# MCU.net
KiCad netlist of a schematic drawn in Altium Designer
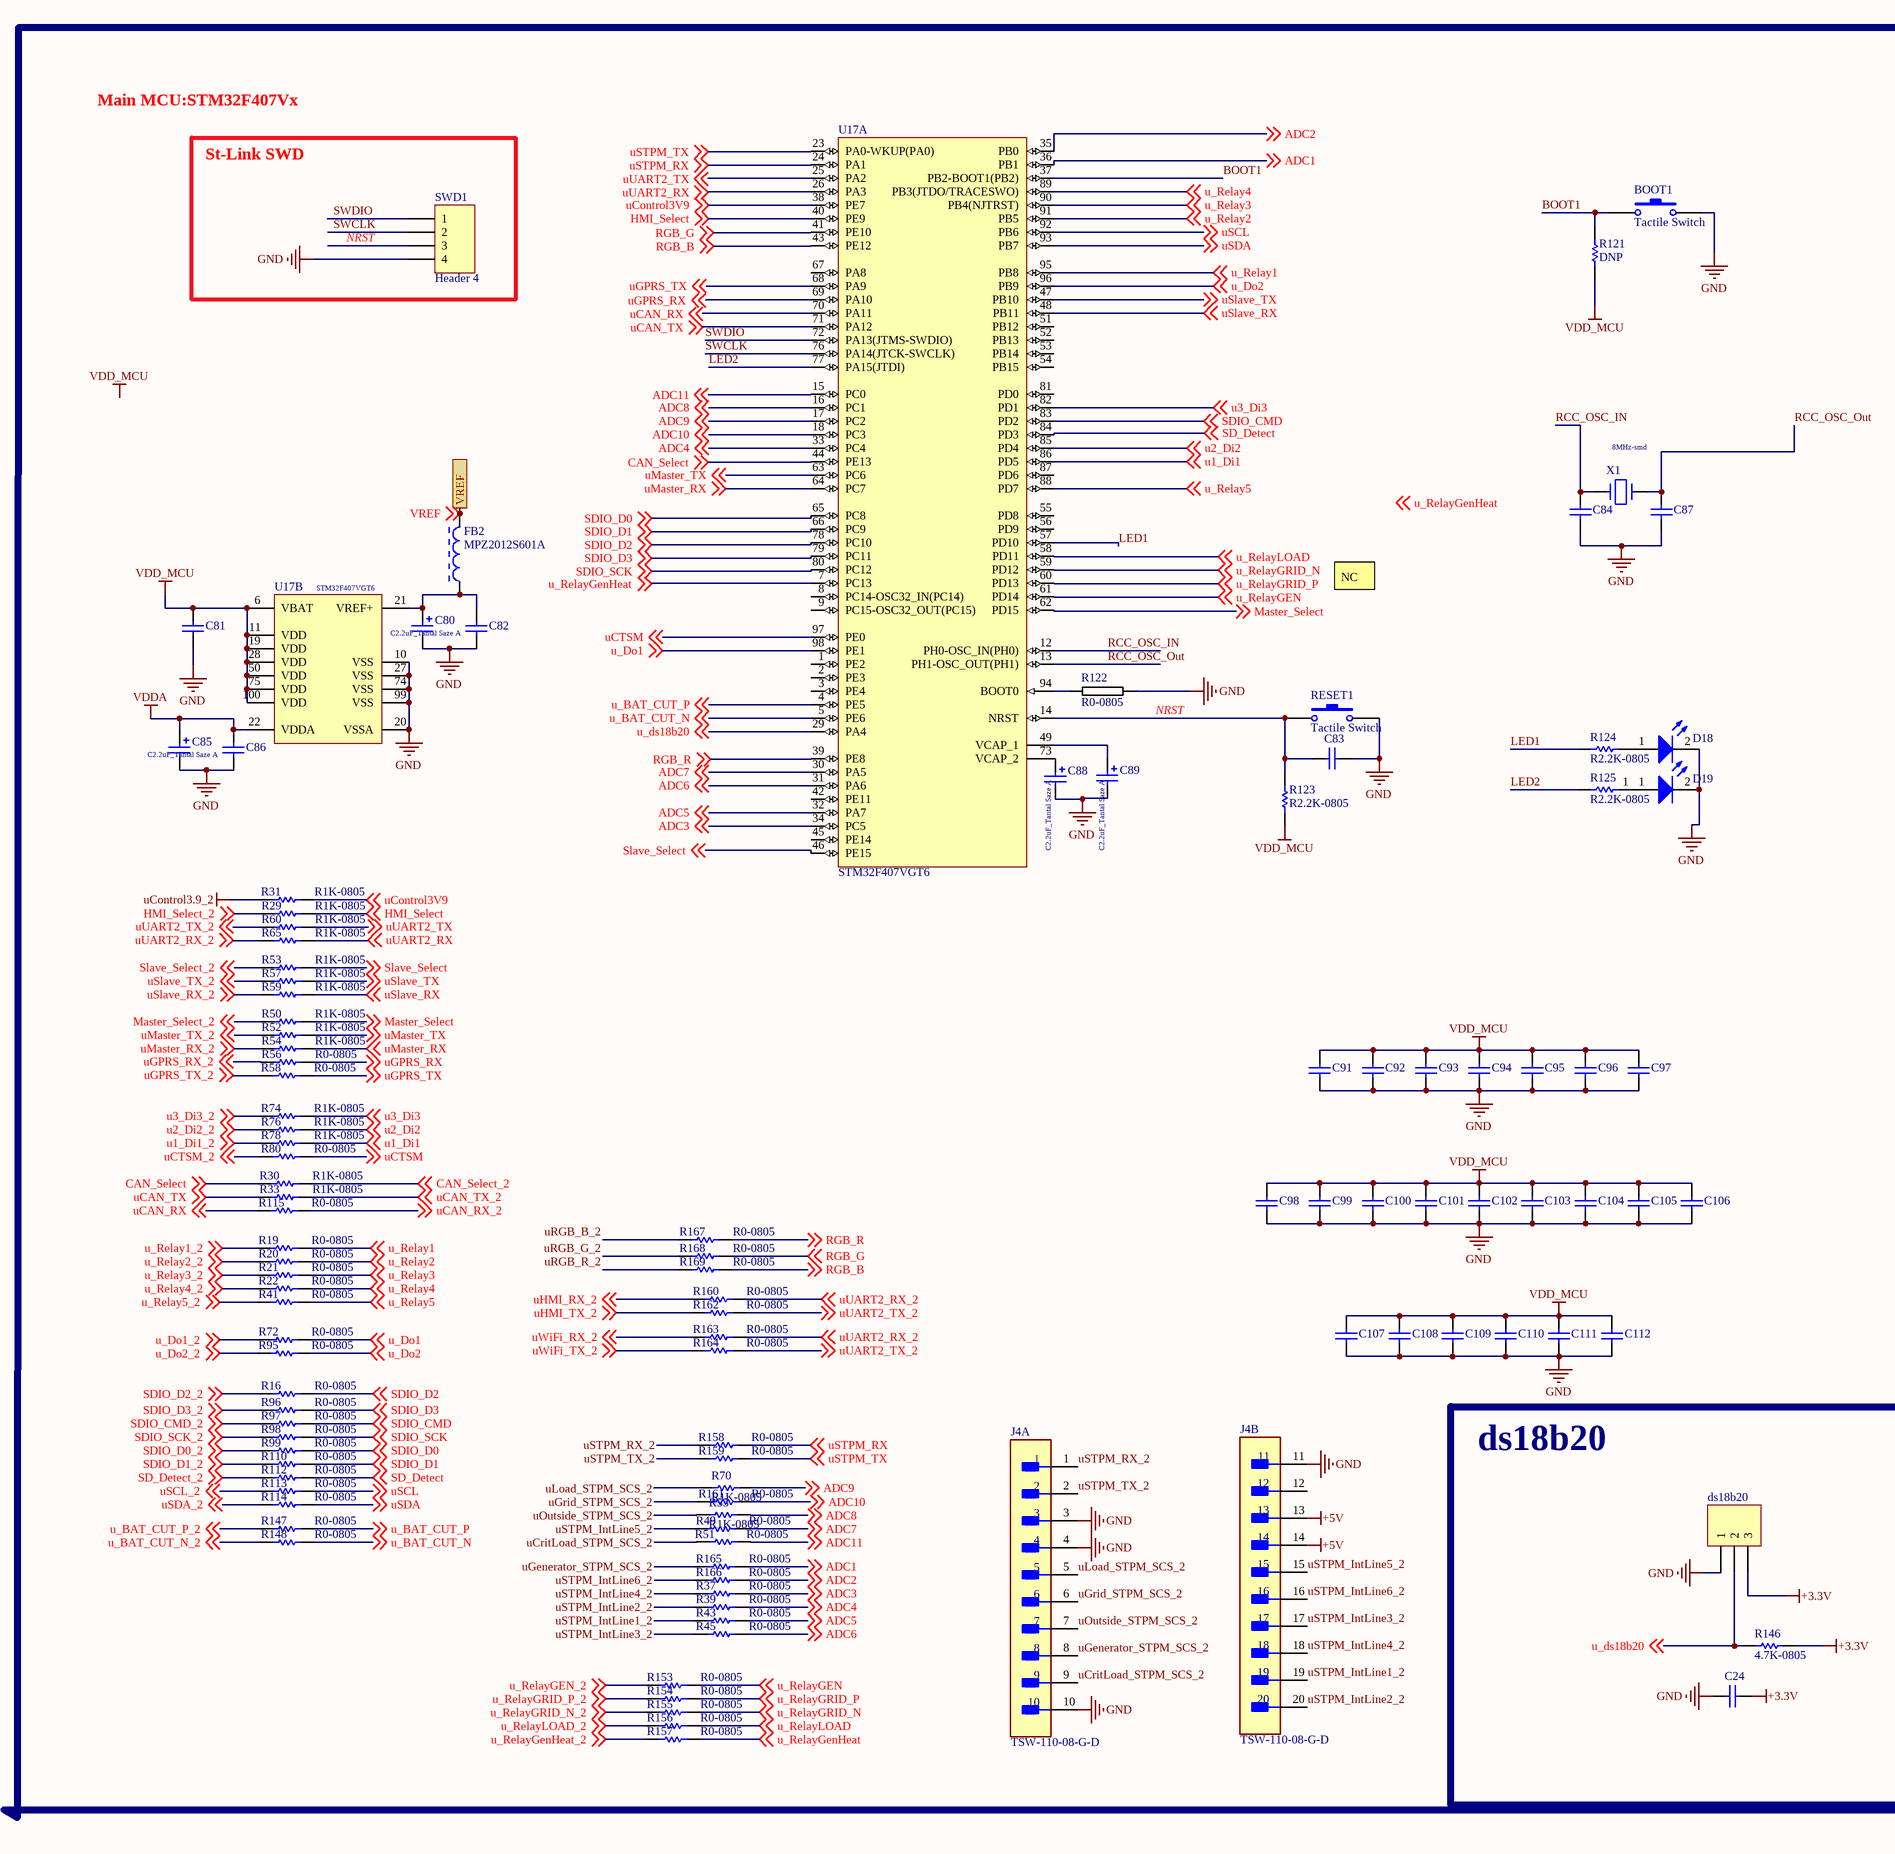
[diagram p0: MCU.SchDoc, left]
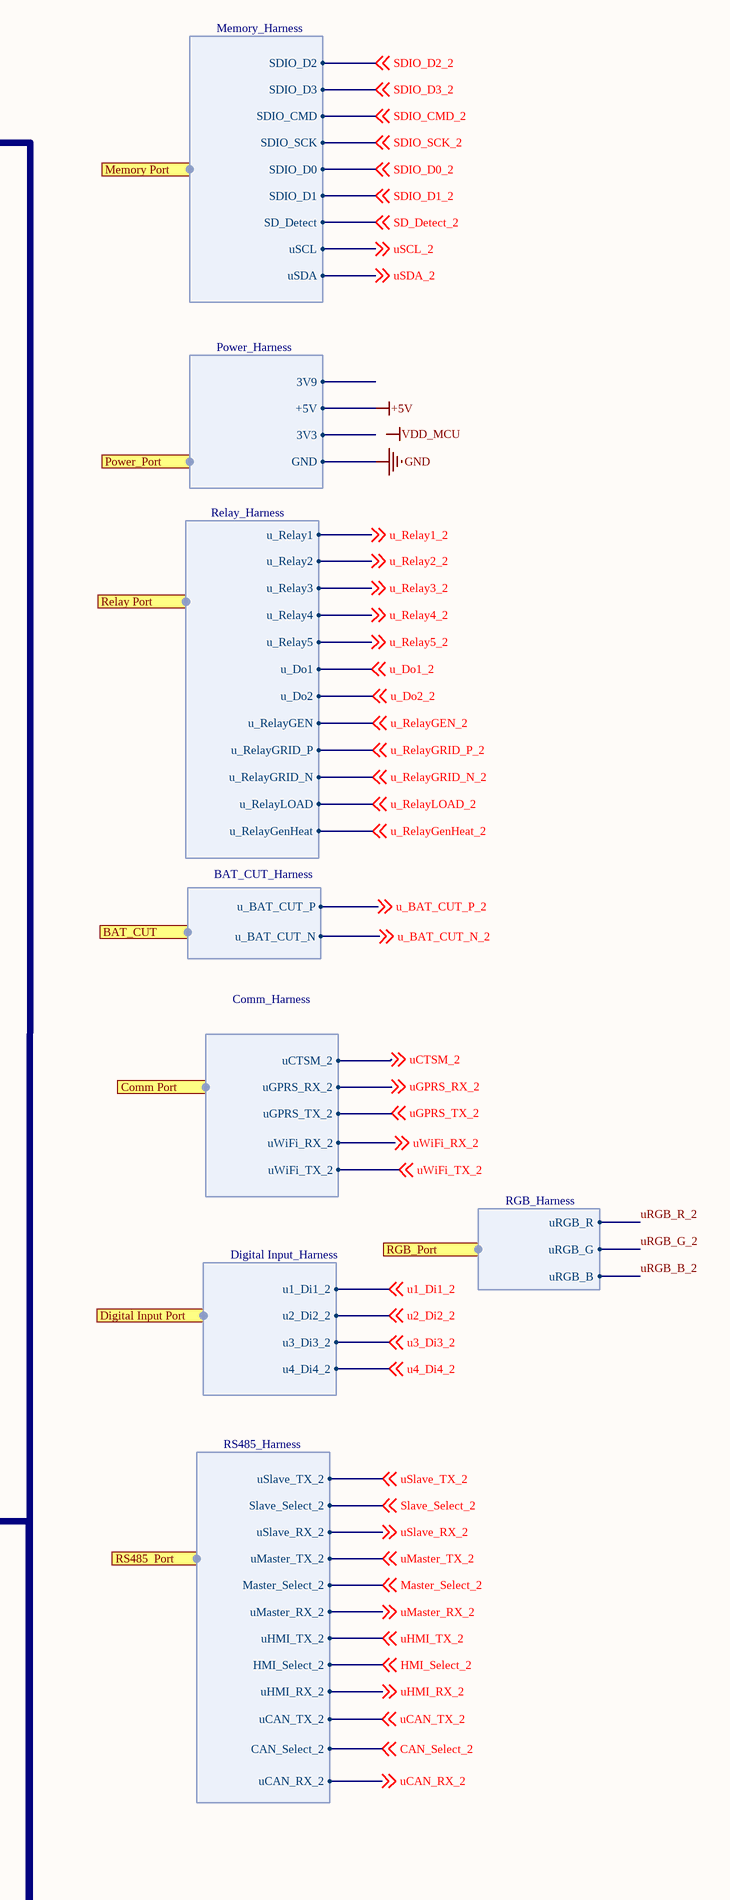
[diagram p1: MCU.SchDoc, right]

(export (version "E")
  (design (tool "Eeschema 10.0.6"))
  (components
    (comp (ref "BOOT1")
      (value "Tactile Switch")
      (footprint "CRF06031")
      (fields (field (name "DIGI-KEY_PART_NUMBER") "732-6992-2-ND"))
      (libsource (lib "My Library") (part "Switch PB"))
    )
    (comp (ref "C24")
      (value "~")
      (footprint "CRF06031")
      (description "Capacitor")
      (fields (field (name "DIGI-KEY_PART_NUMBER") "490-4789-1-ND"))
      (libsource (lib "Miscellaneous Devices") (part "Cap"))
    )
    (comp (ref "C80")
      (value "C2.2uF_Tantal Saze A")
      (footprint "Tantalium Size A")
      (description "Polarized Capacitor,2.2uF,10V,typeA")
      (fields (field (name "DIGI-KEY_PART_NUMBER") "718-2135-2-ND"))
      (libsource (lib "stm32f746Nucleo") (part "Cap_10uF_POL_10%_TANA"))
    )
    (comp (ref "C81")
      (value "~")
      (footprint "CRF06031")
      (description "Capacitor")
      (fields (field (name "DIGI-KEY_PART_NUMBER") "490-4789-1-ND"))
      (libsource (lib "Miscellaneous Devices") (part "Cap"))
    )
    (comp (ref "C82")
      (value "~")
      (footprint "CRF06031")
      (description "Capacitor")
      (fields (field (name "DIGI-KEY_PART_NUMBER") "490-4789-1-ND"))
      (libsource (lib "Miscellaneous Devices") (part "Cap"))
    )
    (comp (ref "C83")
      (value "~")
      (footprint "CRF06031")
      (description "Capacitor")
      (fields (field (name "DIGI-KEY_PART_NUMBER") "490-4789-1-ND"))
      (libsource (lib "Miscellaneous Devices") (part "Cap"))
    )
    (comp (ref "C84")
      (value "~")
      (footprint "CRF06031")
      (description "Capacitor")
      (fields (field (name "DIGI-KEY_PART_NUMBER") "490-5534-2-ND"))
      (libsource (lib "Miscellaneous Devices") (part "Cap"))
    )
    (comp (ref "C85")
      (value "C2.2uF_Tantal Saze A")
      (footprint "Tantalium Size A")
      (description "Polarized Capacitor,2.2uF,10V,typeA")
      (fields (field (name "DIGI-KEY_PART_NUMBER") "718-2135-2-ND"))
      (libsource (lib "stm32f746Nucleo") (part "Cap_10uF_POL_10%_TANA"))
    )
    (comp (ref "C86")
      (value "~")
      (footprint "CRF06031")
      (description "Capacitor")
      (fields (field (name "DIGI-KEY_PART_NUMBER") "490-4789-1-ND"))
      (libsource (lib "Miscellaneous Devices") (part "Cap"))
    )
    (comp (ref "C87")
      (value "~")
      (footprint "CRF06031")
      (description "Capacitor")
      (fields (field (name "DIGI-KEY_PART_NUMBER") "490-5534-2-ND"))
      (libsource (lib "Miscellaneous Devices") (part "Cap"))
    )
    (comp (ref "C88")
      (value "C2.2uF_Tantal Saze A")
      (footprint "Tantalium Size A")
      (description "Polarized Capacitor,2.2uF,10V,typeA")
      (fields (field (name "DIGI-KEY_PART_NUMBER") "718-2135-2-ND"))
      (libsource (lib "stm32f746Nucleo") (part "Cap_10uF_POL_10%_TANA"))
    )
    (comp (ref "C89")
      (value "C2.2uF_Tantal Saze A")
      (footprint "Tantalium Size A")
      (description "Polarized Capacitor,2.2uF,10V,typeA")
      (fields (field (name "DIGI-KEY_PART_NUMBER") "718-2135-2-ND"))
      (libsource (lib "stm32f746Nucleo") (part "Cap_10uF_POL_10%_TANA"))
    )
    (comp (ref "C91")
      (value "~")
      (footprint "CRF06031")
      (description "Capacitor")
      (fields (field (name "DIGI-KEY_PART_NUMBER") "490-4789-1-ND"))
      (libsource (lib "Miscellaneous Devices") (part "Cap"))
    )
    (comp (ref "C92")
      (value "~")
      (footprint "CRF06031")
      (description "Capacitor")
      (fields (field (name "DIGI-KEY_PART_NUMBER") "490-4789-1-ND"))
      (libsource (lib "Miscellaneous Devices") (part "Cap"))
    )
    (comp (ref "C93")
      (value "~")
      (footprint "CRF06031")
      (description "Capacitor")
      (fields (field (name "DIGI-KEY_PART_NUMBER") "490-4789-1-ND"))
      (libsource (lib "Miscellaneous Devices") (part "Cap"))
    )
    (comp (ref "C94")
      (value "~")
      (footprint "CRF06031")
      (description "Capacitor")
      (fields (field (name "DIGI-KEY_PART_NUMBER") "490-4789-1-ND"))
      (libsource (lib "Miscellaneous Devices") (part "Cap"))
    )
    (comp (ref "C95")
      (value "~")
      (footprint "CRF06031")
      (description "Capacitor")
      (fields (field (name "DIGI-KEY_PART_NUMBER") "490-4789-1-ND"))
      (libsource (lib "Miscellaneous Devices") (part "Cap"))
    )
    (comp (ref "C96")
      (value "~")
      (footprint "CRF06031")
      (description "Capacitor")
      (fields (field (name "DIGI-KEY_PART_NUMBER") "490-4789-1-ND"))
      (libsource (lib "Miscellaneous Devices") (part "Cap"))
    )
    (comp (ref "C97")
      (value "~")
      (footprint "CRF06031")
      (description "Capacitor")
      (fields (field (name "DIGI-KEY_PART_NUMBER") "490-4789-1-ND"))
      (libsource (lib "Miscellaneous Devices") (part "Cap"))
    )
    (comp (ref "C98")
      (value "~")
      (footprint "CRF06031")
      (description "Capacitor")
      (fields (field (name "DIGI-KEY_PART_NUMBER") "490-4789-1-ND"))
      (libsource (lib "Miscellaneous Devices") (part "Cap"))
    )
    (comp (ref "C99")
      (value "~")
      (footprint "CRF06031")
      (description "Capacitor")
      (fields (field (name "DIGI-KEY_PART_NUMBER") "490-4789-1-ND"))
      (libsource (lib "Miscellaneous Devices") (part "Cap"))
    )
    (comp (ref "C100")
      (value "~")
      (footprint "CRF06031")
      (description "Capacitor")
      (fields (field (name "DIGI-KEY_PART_NUMBER") "490-4789-1-ND"))
      (libsource (lib "Miscellaneous Devices") (part "Cap"))
    )
    (comp (ref "C101")
      (value "~")
      (footprint "CRF06031")
      (description "Capacitor")
      (fields (field (name "DIGI-KEY_PART_NUMBER") "490-4789-1-ND"))
      (libsource (lib "Miscellaneous Devices") (part "Cap"))
    )
    (comp (ref "C102")
      (value "~")
      (footprint "CRF06031")
      (description "Capacitor")
      (fields (field (name "DIGI-KEY_PART_NUMBER") "490-4789-1-ND"))
      (libsource (lib "Miscellaneous Devices") (part "Cap"))
    )
    (comp (ref "C103")
      (value "~")
      (footprint "CRF06031")
      (description "Capacitor")
      (fields (field (name "DIGI-KEY_PART_NUMBER") "490-4789-1-ND"))
      (libsource (lib "Miscellaneous Devices") (part "Cap"))
    )
    (comp (ref "C104")
      (value "~")
      (footprint "CRF06031")
      (description "Capacitor")
      (fields (field (name "DIGI-KEY_PART_NUMBER") "490-4789-1-ND"))
      (libsource (lib "Miscellaneous Devices") (part "Cap"))
    )
    (comp (ref "C105")
      (value "~")
      (footprint "CRF06031")
      (description "Capacitor")
      (fields (field (name "DIGI-KEY_PART_NUMBER") "490-4789-1-ND"))
      (libsource (lib "Miscellaneous Devices") (part "Cap"))
    )
    (comp (ref "C106")
      (value "~")
      (footprint "CRF06031")
      (description "Capacitor")
      (fields (field (name "DIGI-KEY_PART_NUMBER") "490-4789-1-ND"))
      (libsource (lib "Miscellaneous Devices") (part "Cap"))
    )
    (comp (ref "C107")
      (value "~")
      (footprint "CRF06031")
      (description "Capacitor")
      (fields (field (name "DIGI-KEY_PART_NUMBER") "490-4789-1-ND"))
      (libsource (lib "Miscellaneous Devices") (part "Cap"))
    )
    (comp (ref "C108")
      (value "~")
      (footprint "CRF06031")
      (description "Capacitor")
      (fields (field (name "DIGI-KEY_PART_NUMBER") "490-4789-1-ND"))
      (libsource (lib "Miscellaneous Devices") (part "Cap"))
    )
    (comp (ref "C109")
      (value "~")
      (footprint "CRF06031")
      (description "Capacitor")
      (fields (field (name "DIGI-KEY_PART_NUMBER") "490-4789-1-ND"))
      (libsource (lib "Miscellaneous Devices") (part "Cap"))
    )
    (comp (ref "C110")
      (value "~")
      (footprint "CRF06031")
      (description "Capacitor")
      (fields (field (name "DIGI-KEY_PART_NUMBER") "490-4789-1-ND"))
      (libsource (lib "Miscellaneous Devices") (part "Cap"))
    )
    (comp (ref "C111")
      (value "~")
      (footprint "CRF06031")
      (description "Capacitor")
      (fields (field (name "DIGI-KEY_PART_NUMBER") "490-4789-1-ND"))
      (libsource (lib "Miscellaneous Devices") (part "Cap"))
    )
    (comp (ref "C112")
      (value "~")
      (footprint "CRF06031")
      (description "Capacitor")
      (fields (field (name "DIGI-KEY_PART_NUMBER") "490-4789-1-ND"))
      (libsource (lib "Miscellaneous Devices") (part "Cap"))
    )
    (comp (ref "D18")
      (value "LED_0805_green")
      (footprint "0805-LED")
      (libsource (lib "HosseinLib") (part "LED_0805"))
    )
    (comp (ref "D19")
      (value "LED_0805_red")
      (footprint "0805-LED")
      (libsource (lib "HosseinLib") (part "LED_0805"))
    )
    (comp (ref "ds18b20")
      (value "LM35-DIP")
      (footprint "TO-92 STR")
      (description "LM35-TO92")
      (fields (field (name "DIGI-KEY_PART_NUMBER") "DS18B20+T&RTR-ND"))
      (libsource (lib "Miscellaneous Connectors") (part "Header 3"))
    )
    (comp (ref "FB2")
      (value "MPZ2012S601A")
      (footprint "TDK-MPZ2012_V")
      (fields (field (name "DIGI-KEY_PART_NUMBER") "445-MPZ2012S601AT000TR-ND"))
      (libsource (lib "Altium Content Vault") (part "BEAD-2"))
    )
    (comp (ref "J4")
      (value "TSW-110-08-G-D")
      (footprint "FP-TSW-110-08-G-D-MFG")
      (description "CONN HEADER VERT 20POS 2.54MM")
      (fields
        (field (name "OCTOPART") "https://octopart.com/tsw-110-08-g-d-samtec-272555")
        (field (name "DIGI-KEY_PART_NUMBER") "SAM1036-10-ND")
      )
      (libsource (lib "Altium Content Vault") (part "77e5b6e48cf913a9c6d5f7856d88bd2"))
    )
    (comp (ref "R16")
      (value "R0-0805")
      (footprint "CRF06031")
      (description "Resistor")
      (fields (field (name "DIGI-KEY_PART_NUMBER") "311-0.0CRTR-ND"))
      (libsource (lib "Miscellaneous Devices") (part "Res1"))
    )
    (comp (ref "R19")
      (value "R0-0805")
      (footprint "CRF06031")
      (description "Resistor")
      (fields (field (name "DIGI-KEY_PART_NUMBER") "311-0.0CRTR-ND"))
      (libsource (lib "Miscellaneous Devices") (part "Res1"))
    )
    (comp (ref "R20")
      (value "R0-0805")
      (footprint "CRF06031")
      (description "Resistor")
      (fields (field (name "DIGI-KEY_PART_NUMBER") "311-0.0CRTR-ND"))
      (libsource (lib "Miscellaneous Devices") (part "Res1"))
    )
    (comp (ref "R21")
      (value "R0-0805")
      (footprint "CRF06031")
      (description "Resistor")
      (fields (field (name "DIGI-KEY_PART_NUMBER") "311-0.0CRTR-ND"))
      (libsource (lib "Miscellaneous Devices") (part "Res1"))
    )
    (comp (ref "R22")
      (value "R0-0805")
      (footprint "CRF06031")
      (description "Resistor")
      (fields (field (name "DIGI-KEY_PART_NUMBER") "311-0.0CRTR-ND"))
      (libsource (lib "Miscellaneous Devices") (part "Res1"))
    )
    (comp (ref "R29")
      (value "R1K-0805")
      (footprint "CRF06031")
      (description "Resistor")
      (fields (field (name "DIGI-KEY_PART_NUMBER") "311-1.00KCRTR-ND"))
      (libsource (lib "Miscellaneous Devices") (part "Res1"))
    )
    (comp (ref "R30")
      (value "R1K-0805")
      (footprint "CRF06031")
      (description "Resistor")
      (fields (field (name "DIGI-KEY_PART_NUMBER") "311-1.00KCRTR-ND"))
      (libsource (lib "Miscellaneous Devices") (part "Res1"))
    )
    (comp (ref "R31")
      (value "R1K-0805")
      (footprint "CRF06031")
      (description "Resistor")
      (fields (field (name "DIGI-KEY_PART_NUMBER") "311-1.00KCRTR-ND"))
      (libsource (lib "Miscellaneous Devices") (part "Res1"))
    )
    (comp (ref "R33")
      (value "R1K-0805")
      (footprint "CRF06031")
      (description "Resistor")
      (fields (field (name "DIGI-KEY_PART_NUMBER") "311-1.00KCRTR-ND"))
      (libsource (lib "Miscellaneous Devices") (part "Res1"))
    )
    (comp (ref "R37")
      (value "R0-0805")
      (footprint "CRF06031")
      (description "Resistor")
      (fields (field (name "DIGI-KEY_PART_NUMBER") "311-0.0CRTR-ND"))
      (libsource (lib "Miscellaneous Devices") (part "Res1"))
    )
    (comp (ref "R39")
      (value "R0-0805")
      (footprint "CRF06031")
      (description "Resistor")
      (fields (field (name "DIGI-KEY_PART_NUMBER") "311-0.0CRTR-ND"))
      (libsource (lib "Miscellaneous Devices") (part "Res1"))
    )
    (comp (ref "R41")
      (value "R0-0805")
      (footprint "CRF06031")
      (description "Resistor")
      (fields (field (name "DIGI-KEY_PART_NUMBER") "311-0.0CRTR-ND"))
      (libsource (lib "Miscellaneous Devices") (part "Res1"))
    )
    (comp (ref "R43")
      (value "R0-0805")
      (footprint "CRF06031")
      (description "Resistor")
      (fields (field (name "DIGI-KEY_PART_NUMBER") "311-0.0CRTR-ND"))
      (libsource (lib "Miscellaneous Devices") (part "Res1"))
    )
    (comp (ref "R45")
      (value "R0-0805")
      (footprint "CRF06031")
      (description "Resistor")
      (fields (field (name "DIGI-KEY_PART_NUMBER") "311-0.0CRTR-ND"))
      (libsource (lib "Miscellaneous Devices") (part "Res1"))
    )
    (comp (ref "R49")
      (value "R0-0805")
      (footprint "CRF06031")
      (description "Resistor")
      (fields (field (name "DIGI-KEY_PART_NUMBER") "311-0.0CRTR-ND"))
      (libsource (lib "Miscellaneous Devices") (part "Res1"))
    )
    (comp (ref "R50")
      (value "R1K-0805")
      (footprint "CRF06031")
      (description "Resistor")
      (fields (field (name "DIGI-KEY_PART_NUMBER") "311-1.00KCRTR-ND"))
      (libsource (lib "Miscellaneous Devices") (part "Res1"))
    )
    (comp (ref "R51")
      (value "R0-0805")
      (footprint "CRF06031")
      (description "Resistor")
      (fields (field (name "DIGI-KEY_PART_NUMBER") "311-0.0CRTR-ND"))
      (libsource (lib "Miscellaneous Devices") (part "Res1"))
    )
    (comp (ref "R52")
      (value "R1K-0805")
      (footprint "CRF06031")
      (description "Resistor")
      (fields (field (name "DIGI-KEY_PART_NUMBER") "311-1.00KCRTR-ND"))
      (libsource (lib "Miscellaneous Devices") (part "Res1"))
    )
    (comp (ref "R53")
      (value "R1K-0805")
      (footprint "CRF06031")
      (description "Resistor")
      (fields (field (name "DIGI-KEY_PART_NUMBER") "311-1.00KCRTR-ND"))
      (libsource (lib "Miscellaneous Devices") (part "Res1"))
    )
    (comp (ref "R54")
      (value "R1K-0805")
      (footprint "CRF06031")
      (description "Resistor")
      (fields (field (name "DIGI-KEY_PART_NUMBER") "311-1.00KCRTR-ND"))
      (libsource (lib "Miscellaneous Devices") (part "Res1"))
    )
    (comp (ref "R55")
      (value "R1K-0805")
      (footprint "CRF06031")
      (description "Resistor")
      (fields (field (name "DIGI-KEY_PART_NUMBER") "311-1.00KCRTR-ND"))
      (libsource (lib "Miscellaneous Devices") (part "Res1"))
    )
    (comp (ref "R56")
      (value "R0-0805")
      (footprint "CRF06031")
      (description "Resistor")
      (fields (field (name "DIGI-KEY_PART_NUMBER") "311-0.0CRTR-ND"))
      (libsource (lib "Miscellaneous Devices") (part "Res1"))
    )
    (comp (ref "R57")
      (value "R1K-0805")
      (footprint "CRF06031")
      (description "Resistor")
      (fields (field (name "DIGI-KEY_PART_NUMBER") "311-1.00KCRTR-ND"))
      (libsource (lib "Miscellaneous Devices") (part "Res1"))
    )
    (comp (ref "R58")
      (value "R0-0805")
      (footprint "CRF06031")
      (description "Resistor")
      (fields (field (name "DIGI-KEY_PART_NUMBER") "311-0.0CRTR-ND"))
      (libsource (lib "Miscellaneous Devices") (part "Res1"))
    )
    (comp (ref "R59")
      (value "R1K-0805")
      (footprint "CRF06031")
      (description "Resistor")
      (fields (field (name "DIGI-KEY_PART_NUMBER") "311-1.00KCRTR-ND"))
      (libsource (lib "Miscellaneous Devices") (part "Res1"))
    )
    (comp (ref "R60")
      (value "R1K-0805")
      (footprint "CRF06031")
      (description "Resistor")
      (fields (field (name "DIGI-KEY_PART_NUMBER") "311-1.00KCRTR-ND"))
      (libsource (lib "Miscellaneous Devices") (part "Res1"))
    )
    (comp (ref "R65")
      (value "R1K-0805")
      (footprint "CRF06031")
      (description "Resistor")
      (fields (field (name "DIGI-KEY_PART_NUMBER") "311-1.00KCRTR-ND"))
      (libsource (lib "Miscellaneous Devices") (part "Res1"))
    )
    (comp (ref "R70")
      (value "R1K-0805")
      (footprint "CRF06031")
      (description "Resistor")
      (fields (field (name "DIGI-KEY_PART_NUMBER") "311-1.00KCRTR-ND"))
      (libsource (lib "Miscellaneous Devices") (part "Res1"))
    )
    (comp (ref "R72")
      (value "R0-0805")
      (footprint "CRF06031")
      (description "Resistor")
      (fields (field (name "DIGI-KEY_PART_NUMBER") "311-0.0CRTR-ND"))
      (libsource (lib "Miscellaneous Devices") (part "Res1"))
    )
    (comp (ref "R74")
      (value "R1K-0805")
      (footprint "CRF06031")
      (description "Resistor")
      (fields (field (name "DIGI-KEY_PART_NUMBER") "311-1.00KCRTR-ND"))
      (libsource (lib "Miscellaneous Devices") (part "Res1"))
    )
    (comp (ref "R76")
      (value "R1K-0805")
      (footprint "CRF06031")
      (description "Resistor")
      (fields (field (name "DIGI-KEY_PART_NUMBER") "311-1.00KCRTR-ND"))
      (libsource (lib "Miscellaneous Devices") (part "Res1"))
    )
    (comp (ref "R78")
      (value "R1K-0805")
      (footprint "CRF06031")
      (description "Resistor")
      (fields (field (name "DIGI-KEY_PART_NUMBER") "311-1.00KCRTR-ND"))
      (libsource (lib "Miscellaneous Devices") (part "Res1"))
    )
    (comp (ref "R80")
      (value "R0-0805")
      (footprint "CRF06031")
      (description "Resistor")
      (fields (field (name "DIGI-KEY_PART_NUMBER") "311-0.0CRTR-ND"))
      (libsource (lib "Miscellaneous Devices") (part "Res1"))
    )
    (comp (ref "R95")
      (value "R0-0805")
      (footprint "CRF06031")
      (description "Resistor")
      (fields (field (name "DIGI-KEY_PART_NUMBER") "311-0.0CRTR-ND"))
      (libsource (lib "Miscellaneous Devices") (part "Res1"))
    )
    (comp (ref "R96")
      (value "R0-0805")
      (footprint "CRF06031")
      (description "Resistor")
      (fields (field (name "DIGI-KEY_PART_NUMBER") "311-0.0CRTR-ND"))
      (libsource (lib "Miscellaneous Devices") (part "Res1"))
    )
    (comp (ref "R97")
      (value "R0-0805")
      (footprint "CRF06031")
      (description "Resistor")
      (fields (field (name "DIGI-KEY_PART_NUMBER") "311-0.0CRTR-ND"))
      (libsource (lib "Miscellaneous Devices") (part "Res1"))
    )
    (comp (ref "R98")
      (value "R0-0805")
      (footprint "CRF06031")
      (description "Resistor")
      (fields (field (name "DIGI-KEY_PART_NUMBER") "311-0.0CRTR-ND"))
      (libsource (lib "Miscellaneous Devices") (part "Res1"))
    )
    (comp (ref "R99")
      (value "R0-0805")
      (footprint "CRF06031")
      (description "Resistor")
      (fields (field (name "DIGI-KEY_PART_NUMBER") "311-0.0CRTR-ND"))
      (libsource (lib "Miscellaneous Devices") (part "Res1"))
    )
    (comp (ref "R110")
      (value "R0-0805")
      (footprint "CRF06031")
      (description "Resistor")
      (fields (field (name "DIGI-KEY_PART_NUMBER") "311-0.0CRTR-ND"))
      (libsource (lib "Miscellaneous Devices") (part "Res1"))
    )
    (comp (ref "R112")
      (value "R0-0805")
      (footprint "CRF06031")
      (description "Resistor")
      (fields (field (name "DIGI-KEY_PART_NUMBER") "311-0.0CRTR-ND"))
      (libsource (lib "Miscellaneous Devices") (part "Res1"))
    )
    (comp (ref "R113")
      (value "R0-0805")
      (footprint "CRF06031")
      (description "Resistor")
      (fields (field (name "DIGI-KEY_PART_NUMBER") "311-0.0CRTR-ND"))
      (libsource (lib "Miscellaneous Devices") (part "Res1"))
    )
    (comp (ref "R114")
      (value "R0-0805")
      (footprint "CRF06031")
      (description "Resistor")
      (fields (field (name "DIGI-KEY_PART_NUMBER") "311-0.0CRTR-ND"))
      (libsource (lib "Miscellaneous Devices") (part "Res1"))
    )
    (comp (ref "R115")
      (value "R0-0805")
      (footprint "CRF06031")
      (description "Resistor")
      (fields (field (name "DIGI-KEY_PART_NUMBER") "311-0.0CRTR-ND"))
      (libsource (lib "Miscellaneous Devices") (part "Res1"))
    )
    (comp (ref "R121")
      (value "DNP")
      (footprint "CRF06031")
      (libsource (lib "Miscellaneous Devices") (part "Res1"))
    )
    (comp (ref "R122")
      (value "R0-0805")
      (footprint "CRF06031")
      (description "RESISTOR 0805 1/4 WATT THIN FILM")
      (fields (field (name "DIGI-KEY_PART_NUMBER") "311-0.0CRTR-ND"))
      (libsource (lib "vh_altium_library") (part "0805R-10K"))
    )
    (comp (ref "R123")
      (value "R2.2K-0805")
      (footprint "CRF06031")
      (description "Resistor")
      (fields (field (name "DIGI-KEY_PART_NUMBER") "311-2.20KCRTR-ND"))
      (libsource (lib "Miscellaneous Devices") (part "Res1"))
    )
    (comp (ref "R124")
      (value "R2.2K-0805")
      (footprint "CRF06031")
      (description "Resistor")
      (fields (field (name "DIGI-KEY_PART_NUMBER") "311-2.20KCRTR-ND"))
      (libsource (lib "Miscellaneous Devices") (part "Res1"))
    )
    (comp (ref "R125")
      (value "R2.2K-0805")
      (footprint "CRF06031")
      (description "Resistor")
      (fields (field (name "DIGI-KEY_PART_NUMBER") "311-2.20KCRTR-ND"))
      (libsource (lib "") (part "Res1_1"))
    )
    (comp (ref "R146")
      (value "4.7K-0805")
      (footprint "CRF06031")
      (description "Resistor")
      (fields (field (name "DIGI-KEY_PART_NUMBER") "311-4.70KCRTR-ND"))
      (libsource (lib "Miscellaneous Devices") (part "Res1"))
    )
    (comp (ref "R147")
      (value "R0-0805")
      (footprint "CRF06031")
      (description "Resistor")
      (fields (field (name "DIGI-KEY_PART_NUMBER") "311-0.0CRTR-ND"))
      (libsource (lib "Miscellaneous Devices") (part "Res1"))
    )
    (comp (ref "R148")
      (value "R0-0805")
      (footprint "CRF06031")
      (description "Resistor")
      (fields (field (name "DIGI-KEY_PART_NUMBER") "311-0.0CRTR-ND"))
      (libsource (lib "Miscellaneous Devices") (part "Res1"))
    )
    (comp (ref "R153")
      (value "R0-0805")
      (footprint "CRF06031")
      (description "Resistor")
      (fields (field (name "DIGI-KEY_PART_NUMBER") "311-0.0CRTR-ND"))
      (libsource (lib "Miscellaneous Devices") (part "Res1"))
    )
    (comp (ref "R154")
      (value "R0-0805")
      (footprint "CRF06031")
      (description "Resistor")
      (fields (field (name "DIGI-KEY_PART_NUMBER") "311-0.0CRTR-ND"))
      (libsource (lib "Miscellaneous Devices") (part "Res1"))
    )
    (comp (ref "R155")
      (value "R0-0805")
      (footprint "CRF06031")
      (description "Resistor")
      (fields (field (name "DIGI-KEY_PART_NUMBER") "311-0.0CRTR-ND"))
      (libsource (lib "Miscellaneous Devices") (part "Res1"))
    )
    (comp (ref "R156")
      (value "R0-0805")
      (footprint "CRF06031")
      (description "Resistor")
      (fields (field (name "DIGI-KEY_PART_NUMBER") "311-0.0CRTR-ND"))
      (libsource (lib "Miscellaneous Devices") (part "Res1"))
    )
    (comp (ref "R157")
      (value "R0-0805")
      (footprint "CRF06031")
      (description "Resistor")
      (fields (field (name "DIGI-KEY_PART_NUMBER") "311-0.0CRTR-ND"))
      (libsource (lib "Miscellaneous Devices") (part "Res1"))
    )
    (comp (ref "R158")
      (value "R0-0805")
      (footprint "CRF06031")
      (description "Resistor")
      (fields (field (name "DIGI-KEY_PART_NUMBER") "311-0.0CRTR-ND"))
      (libsource (lib "Miscellaneous Devices") (part "Res1"))
    )
    (comp (ref "R159")
      (value "R0-0805")
      (footprint "CRF06031")
      (description "Resistor")
      (fields (field (name "DIGI-KEY_PART_NUMBER") "311-0.0CRTR-ND"))
      (libsource (lib "Miscellaneous Devices") (part "Res1"))
    )
    (comp (ref "R160")
      (value "R0-0805")
      (footprint "CRF06031")
      (description "Resistor")
      (fields (field (name "DIGI-KEY_PART_NUMBER") "311-0.0CRTR-ND"))
      (libsource (lib "Miscellaneous Devices") (part "Res1"))
    )
    (comp (ref "R161")
      (value "R0-0805")
      (footprint "CRF06031")
      (description "Resistor")
      (fields (field (name "DIGI-KEY_PART_NUMBER") "311-0.0CRTR-ND"))
      (libsource (lib "Miscellaneous Devices") (part "Res1"))
    )
    (comp (ref "R162")
      (value "R0-0805")
      (footprint "CRF06031")
      (description "Resistor")
      (fields (field (name "DIGI-KEY_PART_NUMBER") "311-0.0CRTR-ND"))
      (libsource (lib "Miscellaneous Devices") (part "Res1"))
    )
    (comp (ref "R163")
      (value "R0-0805")
      (footprint "CRF06031")
      (description "Resistor")
      (fields (field (name "DIGI-KEY_PART_NUMBER") "311-0.0CRTR-ND"))
      (libsource (lib "Miscellaneous Devices") (part "Res1"))
    )
    (comp (ref "R164")
      (value "R0-0805")
      (footprint "CRF06031")
      (description "Resistor")
      (fields (field (name "DIGI-KEY_PART_NUMBER") "311-0.0CRTR-ND"))
      (libsource (lib "Miscellaneous Devices") (part "Res1"))
    )
    (comp (ref "R165")
      (value "R0-0805")
      (footprint "CRF06031")
      (description "Resistor")
      (fields (field (name "DIGI-KEY_PART_NUMBER") "311-0.0CRTR-ND"))
      (libsource (lib "Miscellaneous Devices") (part "Res1"))
    )
    (comp (ref "R166")
      (value "R0-0805")
      (footprint "CRF06031")
      (description "Resistor")
      (fields (field (name "DIGI-KEY_PART_NUMBER") "311-0.0CRTR-ND"))
      (libsource (lib "Miscellaneous Devices") (part "Res1"))
    )
    (comp (ref "R167")
      (value "R0-0805")
      (footprint "CRF06031")
      (description "Resistor")
      (fields (field (name "DIGI-KEY_PART_NUMBER") "311-0.0CRTR-ND"))
      (libsource (lib "Miscellaneous Devices") (part "Res1"))
    )
    (comp (ref "R168")
      (value "R0-0805")
      (footprint "CRF06031")
      (description "Resistor")
      (fields (field (name "DIGI-KEY_PART_NUMBER") "311-0.0CRTR-ND"))
      (libsource (lib "Miscellaneous Devices") (part "Res1"))
    )
    (comp (ref "R169")
      (value "R0-0805")
      (footprint "CRF06031")
      (description "Resistor")
      (fields (field (name "DIGI-KEY_PART_NUMBER") "311-0.0CRTR-ND"))
      (libsource (lib "Miscellaneous Devices") (part "Res1"))
    )
    (comp (ref "RESET1")
      (value "Tactile Switch")
      (footprint "CRF06031")
      (fields (field (name "DIGI-KEY_PART_NUMBER") "732-6992-2-ND"))
      (libsource (lib "My Library") (part "Switch PB"))
    )
    (comp (ref "SWD1")
      (value "Header 4")
      (footprint "HDR1X4")
      (description "Header, 4-Pin")
      (libsource (lib "chilla bord") (part "Header 4"))
    )
    (comp (ref "U17")
      (value "STM32F407VGT6")
      (footprint "STM-LQFP100_N")
      (fields (field (name "DIGI-KEY_PART_NUMBER") "497-11605-ND"))
      (libsource (lib "") (part "STM32F407VGT6_1"))
    )
    (comp (ref "X1")
      (value "8MHz-smd")
      (footprint "smd xtal 16M")
      (fields (field (name "DIGI-KEY_PART_NUMBER") "XC1494TR-ND"))
      (libsource (lib "pH_rev3") (part "CRYSTAL"))
    )
  )
  (nets
    (net (code "10") (name "+3.3V") (class "Default")
      (node (ref "C24") (pin "2") (pinfunction "2_2") (pintype "passive"))
      (node (ref "R146") (pin "2") (pinfunction "2_2") (pintype "passive"))
      (node (ref "ds18b20") (pin "3") (pinfunction "3_3") (pintype "passive"))
    )
    (net (code "11") (name "+5V") (class "Default")
      (node (ref "J4") (pin "13") (pinfunction "13_13") (pintype "passive"))
      (node (ref "J4") (pin "14") (pinfunction "14_14") (pintype "passive"))
    )
    (net (code "12") (name "/BOOT1") (class "Default")
      (node (ref "BOOT1") (pin "1") (pinfunction "1_1") (pintype "passive"))
      (node (ref "R121") (pin "2") (pinfunction "2_2") (pintype "passive"))
      (node (ref "U17") (pin "37") (pinfunction "PB2-BOOT1(PB2)_37") (pintype "bidirectional"))
    )
    (net (code "13") (name "/LED1") (class "Default")
      (node (ref "R124") (pin "2") (pinfunction "2_2") (pintype "passive"))
      (node (ref "U17") (pin "57") (pinfunction "PD10_57") (pintype "bidirectional"))
    )
    (net (code "14") (name "/LED2") (class "Default")
      (node (ref "R125") (pin "2") (pinfunction "2_2") (pintype "passive"))
      (node (ref "U17") (pin "77") (pinfunction "PA15(JTDI)_77") (pintype "bidirectional"))
    )
    (net (code "15") (name "/NRST") (class "Default")
      (node (ref "C83") (pin "1") (pinfunction "1_1") (pintype "passive"))
      (node (ref "R123") (pin "2") (pinfunction "2_2") (pintype "passive"))
      (node (ref "RESET1") (pin "1") (pinfunction "1_1") (pintype "passive"))
      (node (ref "SWD1") (pin "3") (pinfunction "3_3") (pintype "passive"))
      (node (ref "U17") (pin "14") (pinfunction "NRST_14") (pintype "bidirectional"))
    )
    (net (code "16") (name "/RCC_OSC_IN") (class "Default")
      (node (ref "C84") (pin "2") (pinfunction "2_2") (pintype "passive"))
      (node (ref "U17") (pin "12") (pinfunction "PH0-OSC_IN(PH0)_12") (pintype "bidirectional"))
      (node (ref "X1") (pin "1") (pintype "passive"))
    )
    (net (code "17") (name "/RCC_OSC_Out") (class "Default")
      (node (ref "C87") (pin "2") (pinfunction "2_2") (pintype "passive"))
      (node (ref "U17") (pin "13") (pinfunction "PH1-OSC_OUT(PH1)_13") (pintype "bidirectional"))
      (node (ref "X1") (pin "2") (pintype "passive"))
    )
    (net (code "18") (name "/SWCLK") (class "Default")
      (node (ref "SWD1") (pin "2") (pinfunction "2_2") (pintype "passive"))
      (node (ref "U17") (pin "76") (pinfunction "PA14(JTCK-SWCLK)_76") (pintype "bidirectional"))
    )
    (net (code "19") (name "/SWDIO") (class "Default")
      (node (ref "SWD1") (pin "1") (pinfunction "1_1") (pintype "passive"))
      (node (ref "U17") (pin "72") (pinfunction "PA13(JTMS-SWDIO)_72") (pintype "bidirectional"))
    )
    (net (code "20") (name "/uCritLoad_STPM_SCS_2") (class "Default")
      (node (ref "J4") (pin "9") (pinfunction "9_9") (pintype "passive"))
      (node (ref "R51") (pin "1") (pinfunction "1_1") (pintype "passive"))
    )
    (net (code "21") (name "/uGenerator_STPM_SCS_2") (class "Default")
      (node (ref "J4") (pin "8") (pinfunction "8_8") (pintype "passive"))
      (node (ref "R165") (pin "2") (pinfunction "2_2") (pintype "passive"))
    )
    (net (code "22") (name "/uGrid_STPM_SCS_2") (class "Default")
      (node (ref "J4") (pin "6") (pinfunction "6_6") (pintype "passive"))
      (node (ref "R161") (pin "2") (pinfunction "2_2") (pintype "passive"))
    )
    (net (code "23") (name "/uLoad_STPM_SCS_2") (class "Default")
      (node (ref "J4") (pin "5") (pinfunction "5_5") (pintype "passive"))
      (node (ref "R70") (pin "1") (pinfunction "1_1") (pintype "passive"))
    )
    (net (code "24") (name "/uOutside_STPM_SCS_2") (class "Default")
      (node (ref "J4") (pin "7") (pinfunction "7_7") (pintype "passive"))
      (node (ref "R55") (pin "1") (pinfunction "1_1") (pintype "passive"))
    )
    (net (code "25") (name "/uRGB_B_2") (class "Default")
      (node (ref "R167") (pin "2") (pinfunction "2_2") (pintype "passive"))
    )
    (net (code "26") (name "/uRGB_G_2") (class "Default")
      (node (ref "R168") (pin "2") (pinfunction "2_2") (pintype "passive"))
    )
    (net (code "27") (name "/uRGB_R_2") (class "Default")
      (node (ref "R169") (pin "2") (pinfunction "2_2") (pintype "passive"))
    )
    (net (code "28") (name "/uSTPM_IntLine1_2") (class "Default")
      (node (ref "J4") (pin "19") (pinfunction "19_19") (pintype "passive"))
      (node (ref "R43") (pin "2") (pinfunction "2_2") (pintype "passive"))
    )
    (net (code "29") (name "/uSTPM_IntLine2_2") (class "Default")
      (node (ref "J4") (pin "20") (pinfunction "20_20") (pintype "passive"))
      (node (ref "R39") (pin "2") (pinfunction "2_2") (pintype "passive"))
    )
    (net (code "30") (name "/uSTPM_IntLine3_2") (class "Default")
      (node (ref "J4") (pin "17") (pinfunction "17_17") (pintype "passive"))
      (node (ref "R45") (pin "2") (pinfunction "2_2") (pintype "passive"))
    )
    (net (code "31") (name "/uSTPM_IntLine4_2") (class "Default")
      (node (ref "J4") (pin "18") (pinfunction "18_18") (pintype "passive"))
      (node (ref "R37") (pin "2") (pinfunction "2_2") (pintype "passive"))
    )
    (net (code "32") (name "/uSTPM_IntLine5_2") (class "Default")
      (node (ref "J4") (pin "15") (pinfunction "15_15") (pintype "passive"))
      (node (ref "R49") (pin "2") (pinfunction "2_2") (pintype "passive"))
    )
    (net (code "33") (name "/uSTPM_IntLine6_2") (class "Default")
      (node (ref "J4") (pin "16") (pinfunction "16_16") (pintype "passive"))
      (node (ref "R166") (pin "2") (pinfunction "2_2") (pintype "passive"))
    )
    (net (code "34") (name "/uSTPM_RX_2") (class "Default")
      (node (ref "J4") (pin "1") (pinfunction "1_1") (pintype "passive"))
      (node (ref "R158") (pin "2") (pinfunction "2_2") (pintype "passive"))
    )
    (net (code "35") (name "/uSTPM_TX_2") (class "Default")
      (node (ref "J4") (pin "2") (pinfunction "2_2") (pintype "passive"))
      (node (ref "R159") (pin "2") (pinfunction "2_2") (pintype "passive"))
    )
    (net (code "44") (name "ADC1") (class "Default")
      (node (ref "R165") (pin "1") (pinfunction "1_1") (pintype "passive"))
      (node (ref "U17") (pin "36") (pinfunction "PB1_36") (pintype "bidirectional"))
    )
    (net (code "45") (name "ADC2") (class "Default")
      (node (ref "R166") (pin "1") (pinfunction "1_1") (pintype "passive"))
      (node (ref "U17") (pin "35") (pinfunction "PB0_35") (pintype "bidirectional"))
    )
    (net (code "46") (name "ADC3") (class "Default")
      (node (ref "R37") (pin "1") (pinfunction "1_1") (pintype "passive"))
      (node (ref "U17") (pin "34") (pinfunction "PC5_34") (pintype "bidirectional"))
    )
    (net (code "47") (name "ADC4") (class "Default")
      (node (ref "R39") (pin "1") (pinfunction "1_1") (pintype "passive"))
      (node (ref "U17") (pin "33") (pinfunction "PC4_33") (pintype "bidirectional"))
    )
    (net (code "48") (name "ADC5") (class "Default")
      (node (ref "R43") (pin "1") (pinfunction "1_1") (pintype "passive"))
      (node (ref "U17") (pin "32") (pinfunction "PA7_32") (pintype "bidirectional"))
    )
    (net (code "49") (name "ADC6") (class "Default")
      (node (ref "R45") (pin "1") (pinfunction "1_1") (pintype "passive"))
      (node (ref "U17") (pin "31") (pinfunction "PA6_31") (pintype "bidirectional"))
    )
    (net (code "50") (name "ADC7") (class "Default")
      (node (ref "R49") (pin "1") (pinfunction "1_1") (pintype "passive"))
      (node (ref "U17") (pin "30") (pinfunction "PA5_30") (pintype "bidirectional"))
    )
    (net (code "51") (name "ADC8") (class "Default")
      (node (ref "R55") (pin "2") (pinfunction "2_2") (pintype "passive"))
      (node (ref "U17") (pin "16") (pinfunction "PC1_16") (pintype "bidirectional"))
    )
    (net (code "52") (name "ADC9") (class "Default")
      (node (ref "R70") (pin "2") (pinfunction "2_2") (pintype "passive"))
      (node (ref "U17") (pin "17") (pinfunction "PC2_17") (pintype "bidirectional"))
    )
    (net (code "53") (name "ADC10") (class "Default")
      (node (ref "R161") (pin "1") (pinfunction "1_1") (pintype "passive"))
      (node (ref "U17") (pin "18") (pinfunction "PC3_18") (pintype "bidirectional"))
    )
    (net (code "54") (name "ADC11") (class "Default")
      (node (ref "R51") (pin "2") (pinfunction "2_2") (pintype "passive"))
      (node (ref "U17") (pin "15") (pinfunction "PC0_15") (pintype "bidirectional"))
    )
    (net (code "55") (name "CAN_Select") (class "Default")
      (node (ref "R30") (pin "2") (pinfunction "2_2") (pintype "passive"))
      (node (ref "U17") (pin "44") (pinfunction "PE13_44") (pintype "bidirectional"))
    )
    (net (code "56") (name "CAN_Select_2") (class "Default")
      (node (ref "R30") (pin "1") (pinfunction "1_1") (pintype "passive"))
    )
    (net (code "57") (name "GND") (class "Default")
      (node (ref "BOOT1") (pin "2") (pinfunction "2_2") (pintype "passive"))
      (node (ref "C100") (pin "2") (pinfunction "2_2") (pintype "passive"))
      (node (ref "C101") (pin "2") (pinfunction "2_2") (pintype "passive"))
      (node (ref "C102") (pin "2") (pinfunction "2_2") (pintype "passive"))
      (node (ref "C103") (pin "2") (pinfunction "2_2") (pintype "passive"))
      (node (ref "C104") (pin "2") (pinfunction "2_2") (pintype "passive"))
      (node (ref "C105") (pin "2") (pinfunction "2_2") (pintype "passive"))
      (node (ref "C106") (pin "2") (pinfunction "2_2") (pintype "passive"))
      (node (ref "C107") (pin "2") (pinfunction "2_2") (pintype "passive"))
      (node (ref "C108") (pin "2") (pinfunction "2_2") (pintype "passive"))
      (node (ref "C109") (pin "2") (pinfunction "2_2") (pintype "passive"))
      (node (ref "C110") (pin "2") (pinfunction "2_2") (pintype "passive"))
      (node (ref "C111") (pin "2") (pinfunction "2_2") (pintype "passive"))
      (node (ref "C112") (pin "2") (pinfunction "2_2") (pintype "passive"))
      (node (ref "C24") (pin "1") (pinfunction "1_1") (pintype "passive"))
      (node (ref "C80") (pin "2") (pinfunction "2_2") (pintype "passive"))
      (node (ref "C81") (pin "2") (pinfunction "2_2") (pintype "passive"))
      (node (ref "C82") (pin "2") (pinfunction "2_2") (pintype "passive"))
      (node (ref "C83") (pin "2") (pinfunction "2_2") (pintype "passive"))
      (node (ref "C84") (pin "1") (pinfunction "1_1") (pintype "passive"))
      (node (ref "C85") (pin "2") (pinfunction "2_2") (pintype "passive"))
      (node (ref "C86") (pin "2") (pinfunction "2_2") (pintype "passive"))
      (node (ref "C87") (pin "1") (pinfunction "1_1") (pintype "passive"))
      (node (ref "C88") (pin "2") (pinfunction "2_2") (pintype "passive"))
      (node (ref "C89") (pin "2") (pinfunction "2_2") (pintype "passive"))
      (node (ref "C91") (pin "2") (pinfunction "2_2") (pintype "passive"))
      (node (ref "C92") (pin "2") (pinfunction "2_2") (pintype "passive"))
      (node (ref "C93") (pin "2") (pinfunction "2_2") (pintype "passive"))
      (node (ref "C94") (pin "2") (pinfunction "2_2") (pintype "passive"))
      (node (ref "C95") (pin "2") (pinfunction "2_2") (pintype "passive"))
      (node (ref "C96") (pin "2") (pinfunction "2_2") (pintype "passive"))
      (node (ref "C97") (pin "2") (pinfunction "2_2") (pintype "passive"))
      (node (ref "C98") (pin "2") (pinfunction "2_2") (pintype "passive"))
      (node (ref "C99") (pin "2") (pinfunction "2_2") (pintype "passive"))
      (node (ref "D18") (pin "2") (pinfunction "K_2") (pintype "passive"))
      (node (ref "D19") (pin "2") (pinfunction "K_2") (pintype "passive"))
      (node (ref "J4") (pin "10") (pinfunction "10_10") (pintype "passive"))
      (node (ref "J4") (pin "11") (pinfunction "11_11") (pintype "passive"))
      (node (ref "J4") (pin "3") (pinfunction "3_3") (pintype "passive"))
      (node (ref "J4") (pin "4") (pinfunction "4_4") (pintype "passive"))
      (node (ref "R122") (pin "2") (pintype "passive"))
      (node (ref "RESET1") (pin "2") (pinfunction "2_2") (pintype "passive"))
      (node (ref "SWD1") (pin "4") (pinfunction "4_4") (pintype "passive"))
      (node (ref "U17") (pin "10") (pinfunction "VSS_10") (pintype "power_in"))
      (node (ref "U17") (pin "20") (pinfunction "VSSA_20") (pintype "power_in"))
      (node (ref "U17") (pin "27") (pinfunction "VSS_27") (pintype "power_in"))
      (node (ref "U17") (pin "74") (pinfunction "VSS_74") (pintype "power_in"))
      (node (ref "U17") (pin "99") (pinfunction "VSS_99") (pintype "power_in"))
      (node (ref "ds18b20") (pin "1") (pinfunction "1_1") (pintype "passive"))
    )
    (net (code "58") (name "HMI_Select") (class "Default")
      (node (ref "R29") (pin "1") (pinfunction "1_1") (pintype "passive"))
      (node (ref "U17") (pin "40") (pinfunction "PE9_40") (pintype "bidirectional"))
    )
    (net (code "59") (name "HMI_Select_2") (class "Default")
      (node (ref "R29") (pin "2") (pinfunction "2_2") (pintype "passive"))
    )
    (net (code "60") (name "Master_Select") (class "Default")
      (node (ref "R50") (pin "1") (pinfunction "1_1") (pintype "passive"))
      (node (ref "U17") (pin "62") (pinfunction "PD15_62") (pintype "bidirectional"))
    )
    (net (code "61") (name "Master_Select_2") (class "Default")
      (node (ref "R50") (pin "2") (pinfunction "2_2") (pintype "passive"))
    )
    (net (code "62") (name "Net-(D18-A)") (class "Default")
      (node (ref "D18") (pin "1") (pinfunction "A_1") (pintype "passive"))
      (node (ref "R124") (pin "1") (pinfunction "1_1") (pintype "passive"))
    )
    (net (code "63") (name "Net-(D19-A)") (class "Default")
      (node (ref "D19") (pin "1") (pinfunction "A_1") (pintype "passive"))
      (node (ref "R125") (pin "1") (pinfunction "1_1") (pintype "passive"))
    )
    (net (code "64") (name "Net-(U17A-BOOT0)") (class "Default")
      (node (ref "R122") (pin "1") (pintype "passive"))
      (node (ref "U17") (pin "94") (pinfunction "BOOT0_94") (pintype "input"))
    )
    (net (code "65") (name "Net-(U17A-VCAP_1)") (class "Default")
      (node (ref "C89") (pin "1") (pinfunction "1_1") (pintype "passive"))
      (node (ref "U17") (pin "49") (pinfunction "VCAP_1_49") (pintype "power_in"))
    )
    (net (code "66") (name "Net-(U17A-VCAP_2)") (class "Default")
      (node (ref "C88") (pin "1") (pinfunction "1_1") (pintype "passive"))
      (node (ref "U17") (pin "73") (pinfunction "VCAP_2_73") (pintype "power_in"))
    )
    (net (code "67") (name "Net-(U17B-VREF+)") (class "Default")
      (node (ref "C80") (pin "1") (pinfunction "1_1") (pintype "passive"))
      (node (ref "C82") (pin "1") (pinfunction "1_1") (pintype "passive"))
      (node (ref "FB2") (pin "1") (pinfunction "1_1") (pintype "passive"))
      (node (ref "U17") (pin "21") (pinfunction "VREF+_21") (pintype "power_in"))
    )
    (net (code "68") (name "RGB_B") (class "Default")
      (node (ref "R169") (pin "1") (pinfunction "1_1") (pintype "passive"))
      (node (ref "U17") (pin "43") (pinfunction "PE12_43") (pintype "bidirectional"))
    )
    (net (code "69") (name "RGB_G") (class "Default")
      (node (ref "R168") (pin "1") (pinfunction "1_1") (pintype "passive"))
      (node (ref "U17") (pin "41") (pinfunction "PE10_41") (pintype "bidirectional"))
    )
    (net (code "70") (name "RGB_R") (class "Default")
      (node (ref "R167") (pin "1") (pinfunction "1_1") (pintype "passive"))
      (node (ref "U17") (pin "39") (pinfunction "PE8_39") (pintype "bidirectional"))
    )
    (net (code "71") (name "SDIO_CMD") (class "Default")
      (node (ref "R97") (pin "1") (pinfunction "1_1") (pintype "passive"))
      (node (ref "U17") (pin "83") (pinfunction "PD2_83") (pintype "bidirectional"))
    )
    (net (code "72") (name "SDIO_CMD_2") (class "Default")
      (node (ref "R97") (pin "2") (pinfunction "2_2") (pintype "passive"))
    )
    (net (code "73") (name "SDIO_D0") (class "Default")
      (node (ref "R99") (pin "1") (pinfunction "1_1") (pintype "passive"))
      (node (ref "U17") (pin "65") (pinfunction "PC8_65") (pintype "bidirectional"))
    )
    (net (code "74") (name "SDIO_D0_2") (class "Default")
      (node (ref "R99") (pin "2") (pinfunction "2_2") (pintype "passive"))
    )
    (net (code "75") (name "SDIO_D1") (class "Default")
      (node (ref "R110") (pin "1") (pinfunction "1_1") (pintype "passive"))
      (node (ref "U17") (pin "66") (pinfunction "PC9_66") (pintype "bidirectional"))
    )
    (net (code "76") (name "SDIO_D1_2") (class "Default")
      (node (ref "R110") (pin "2") (pinfunction "2_2") (pintype "passive"))
    )
    (net (code "77") (name "SDIO_D2") (class "Default")
      (node (ref "R16") (pin "1") (pinfunction "1_1") (pintype "passive"))
      (node (ref "U17") (pin "78") (pinfunction "PC10_78") (pintype "bidirectional"))
    )
    (net (code "78") (name "SDIO_D2_2") (class "Default")
      (node (ref "R16") (pin "2") (pinfunction "2_2") (pintype "passive"))
    )
    (net (code "79") (name "SDIO_D3") (class "Default")
      (node (ref "R96") (pin "1") (pinfunction "1_1") (pintype "passive"))
      (node (ref "U17") (pin "79") (pinfunction "PC11_79") (pintype "bidirectional"))
    )
    (net (code "80") (name "SDIO_D3_2") (class "Default")
      (node (ref "R96") (pin "2") (pinfunction "2_2") (pintype "passive"))
    )
    (net (code "81") (name "SDIO_SCK") (class "Default")
      (node (ref "R98") (pin "1") (pinfunction "1_1") (pintype "passive"))
      (node (ref "U17") (pin "80") (pinfunction "PC12_80") (pintype "bidirectional"))
    )
    (net (code "82") (name "SDIO_SCK_2") (class "Default")
      (node (ref "R98") (pin "2") (pinfunction "2_2") (pintype "passive"))
    )
    (net (code "83") (name "SD_Detect") (class "Default")
      (node (ref "R112") (pin "1") (pinfunction "1_1") (pintype "passive"))
      (node (ref "U17") (pin "84") (pinfunction "PD3_84") (pintype "bidirectional"))
    )
    (net (code "84") (name "SD_Detect_2") (class "Default")
      (node (ref "R112") (pin "2") (pinfunction "2_2") (pintype "passive"))
    )
    (net (code "85") (name "Slave_Select") (class "Default")
      (node (ref "R53") (pin "1") (pinfunction "1_1") (pintype "passive"))
      (node (ref "U17") (pin "46") (pinfunction "PE15_46") (pintype "bidirectional"))
    )
    (net (code "86") (name "Slave_Select_2") (class "Default")
      (node (ref "R53") (pin "2") (pinfunction "2_2") (pintype "passive"))
    )
    (net (code "87") (name "VDDA") (class "Default")
      (node (ref "C85") (pin "1") (pinfunction "1_1") (pintype "passive"))
      (node (ref "C86") (pin "1") (pinfunction "1_1") (pintype "passive"))
      (node (ref "U17") (pin "22") (pinfunction "VDDA_22") (pintype "power_in"))
    )
    (net (code "88") (name "VDD_MCU") (class "Default")
      (node (ref "C100") (pin "1") (pinfunction "1_1") (pintype "passive"))
      (node (ref "C101") (pin "1") (pinfunction "1_1") (pintype "passive"))
      (node (ref "C102") (pin "1") (pinfunction "1_1") (pintype "passive"))
      (node (ref "C103") (pin "1") (pinfunction "1_1") (pintype "passive"))
      (node (ref "C104") (pin "1") (pinfunction "1_1") (pintype "passive"))
      (node (ref "C105") (pin "1") (pinfunction "1_1") (pintype "passive"))
      (node (ref "C106") (pin "1") (pinfunction "1_1") (pintype "passive"))
      (node (ref "C107") (pin "1") (pinfunction "1_1") (pintype "passive"))
      (node (ref "C108") (pin "1") (pinfunction "1_1") (pintype "passive"))
      (node (ref "C109") (pin "1") (pinfunction "1_1") (pintype "passive"))
      (node (ref "C110") (pin "1") (pinfunction "1_1") (pintype "passive"))
      (node (ref "C111") (pin "1") (pinfunction "1_1") (pintype "passive"))
      (node (ref "C112") (pin "1") (pinfunction "1_1") (pintype "passive"))
      (node (ref "C81") (pin "1") (pinfunction "1_1") (pintype "passive"))
      (node (ref "C91") (pin "1") (pinfunction "1_1") (pintype "passive"))
      (node (ref "C92") (pin "1") (pinfunction "1_1") (pintype "passive"))
      (node (ref "C93") (pin "1") (pinfunction "1_1") (pintype "passive"))
      (node (ref "C94") (pin "1") (pinfunction "1_1") (pintype "passive"))
      (node (ref "C95") (pin "1") (pinfunction "1_1") (pintype "passive"))
      (node (ref "C96") (pin "1") (pinfunction "1_1") (pintype "passive"))
      (node (ref "C97") (pin "1") (pinfunction "1_1") (pintype "passive"))
      (node (ref "C98") (pin "1") (pinfunction "1_1") (pintype "passive"))
      (node (ref "C99") (pin "1") (pinfunction "1_1") (pintype "passive"))
      (node (ref "R121") (pin "1") (pinfunction "1_1") (pintype "passive"))
      (node (ref "R123") (pin "1") (pinfunction "1_1") (pintype "passive"))
      (node (ref "U17") (pin "100") (pinfunction "VDD_100") (pintype "power_in"))
      (node (ref "U17") (pin "11") (pinfunction "VDD_11") (pintype "power_in"))
      (node (ref "U17") (pin "19") (pinfunction "VDD_19") (pintype "power_in"))
      (node (ref "U17") (pin "28") (pinfunction "VDD_28") (pintype "power_in"))
      (node (ref "U17") (pin "50") (pinfunction "VDD_50") (pintype "power_in"))
      (node (ref "U17") (pin "6") (pinfunction "VBAT_6") (pintype "power_in"))
      (node (ref "U17") (pin "75") (pinfunction "VDD_75") (pintype "power_in"))
    )
    (net (code "89") (name "VREF") (class "Default")
      (node (ref "FB2") (pin "2") (pinfunction "2_2") (pintype "passive"))
    )
    (net (code "90") (name "u1_Di1") (class "Default")
      (node (ref "R78") (pin "1") (pinfunction "1_1") (pintype "passive"))
      (node (ref "U17") (pin "86") (pinfunction "PD5_86") (pintype "bidirectional"))
    )
    (net (code "91") (name "u1_Di1_2") (class "Default")
      (node (ref "R78") (pin "2") (pinfunction "2_2") (pintype "passive"))
    )
    (net (code "92") (name "u2_Di2") (class "Default")
      (node (ref "R76") (pin "1") (pinfunction "1_1") (pintype "passive"))
      (node (ref "U17") (pin "85") (pinfunction "PD4_85") (pintype "bidirectional"))
    )
    (net (code "93") (name "u2_Di2_2") (class "Default")
      (node (ref "R76") (pin "2") (pinfunction "2_2") (pintype "passive"))
    )
    (net (code "94") (name "u3_Di3") (class "Default")
      (node (ref "R74") (pin "1") (pinfunction "1_1") (pintype "passive"))
      (node (ref "U17") (pin "82") (pinfunction "PD1_82") (pintype "bidirectional"))
    )
    (net (code "95") (name "u3_Di3_2") (class "Default")
      (node (ref "R74") (pin "2") (pinfunction "2_2") (pintype "passive"))
    )
    (net (code "97") (name "uCAN_RX") (class "Default")
      (node (ref "R115") (pin "2") (pinfunction "2_2") (pintype "passive"))
      (node (ref "U17") (pin "70") (pinfunction "PA11_70") (pintype "bidirectional"))
    )
    (net (code "98") (name "uCAN_RX_2") (class "Default")
      (node (ref "R115") (pin "1") (pinfunction "1_1") (pintype "passive"))
    )
    (net (code "99") (name "uCAN_TX") (class "Default")
      (node (ref "R33") (pin "2") (pinfunction "2_2") (pintype "passive"))
      (node (ref "U17") (pin "71") (pinfunction "PA12_71") (pintype "bidirectional"))
    )
    (net (code "100") (name "uCAN_TX_2") (class "Default")
      (node (ref "R33") (pin "1") (pinfunction "1_1") (pintype "passive"))
    )
    (net (code "101") (name "uCTSM") (class "Default")
      (node (ref "R80") (pin "1") (pinfunction "1_1") (pintype "passive"))
      (node (ref "U17") (pin "97") (pinfunction "PE0_97") (pintype "bidirectional"))
    )
    (net (code "102") (name "uCTSM_2") (class "Default")
      (node (ref "R80") (pin "2") (pinfunction "2_2") (pintype "passive"))
    )
    (net (code "103") (name "uControl3.9_2") (class "Default")
      (node (ref "R31") (pin "2") (pinfunction "2_2") (pintype "passive"))
    )
    (net (code "104") (name "uControl3V9") (class "Default")
      (node (ref "R31") (pin "1") (pinfunction "1_1") (pintype "passive"))
      (node (ref "U17") (pin "38") (pinfunction "PE7_38") (pintype "bidirectional"))
    )
    (net (code "105") (name "uGPRS_RX") (class "Default")
      (node (ref "R56") (pin "1") (pinfunction "1_1") (pintype "passive"))
      (node (ref "U17") (pin "69") (pinfunction "PA10_69") (pintype "bidirectional"))
    )
    (net (code "106") (name "uGPRS_RX_2") (class "Default")
      (node (ref "R56") (pin "2") (pinfunction "2_2") (pintype "passive"))
    )
    (net (code "107") (name "uGPRS_TX") (class "Default")
      (node (ref "R58") (pin "1") (pinfunction "1_1") (pintype "passive"))
      (node (ref "U17") (pin "68") (pinfunction "PA9_68") (pintype "bidirectional"))
    )
    (net (code "108") (name "uGPRS_TX_2") (class "Default")
      (node (ref "R58") (pin "2") (pinfunction "2_2") (pintype "passive"))
    )
    (net (code "109") (name "uHMI_RX_2") (class "Default")
      (node (ref "R160") (pin "2") (pinfunction "2_2") (pintype "passive"))
    )
    (net (code "110") (name "uHMI_TX_2") (class "Default")
      (node (ref "R162") (pin "2") (pinfunction "2_2") (pintype "passive"))
    )
    (net (code "111") (name "uMaster_RX") (class "Default")
      (node (ref "R54") (pin "1") (pinfunction "1_1") (pintype "passive"))
      (node (ref "U17") (pin "64") (pinfunction "PC7_64") (pintype "bidirectional"))
    )
    (net (code "112") (name "uMaster_RX_2") (class "Default")
      (node (ref "R54") (pin "2") (pinfunction "2_2") (pintype "passive"))
    )
    (net (code "113") (name "uMaster_TX") (class "Default")
      (node (ref "R52") (pin "1") (pinfunction "1_1") (pintype "passive"))
      (node (ref "U17") (pin "63") (pinfunction "PC6_63") (pintype "bidirectional"))
    )
    (net (code "114") (name "uMaster_TX_2") (class "Default")
      (node (ref "R52") (pin "2") (pinfunction "2_2") (pintype "passive"))
    )
    (net (code "115") (name "uSCL") (class "Default")
      (node (ref "R113") (pin "1") (pinfunction "1_1") (pintype "passive"))
      (node (ref "U17") (pin "92") (pinfunction "PB6_92") (pintype "bidirectional"))
    )
    (net (code "116") (name "uSCL_2") (class "Default")
      (node (ref "R113") (pin "2") (pinfunction "2_2") (pintype "passive"))
    )
    (net (code "117") (name "uSDA") (class "Default")
      (node (ref "R114") (pin "1") (pinfunction "1_1") (pintype "passive"))
      (node (ref "U17") (pin "93") (pinfunction "PB7_93") (pintype "bidirectional"))
    )
    (net (code "118") (name "uSDA_2") (class "Default")
      (node (ref "R114") (pin "2") (pinfunction "2_2") (pintype "passive"))
    )
    (net (code "119") (name "uSTPM_RX") (class "Default")
      (node (ref "R158") (pin "1") (pinfunction "1_1") (pintype "passive"))
      (node (ref "U17") (pin "24") (pinfunction "PA1_24") (pintype "bidirectional"))
    )
    (net (code "120") (name "uSTPM_TX") (class "Default")
      (node (ref "R159") (pin "1") (pinfunction "1_1") (pintype "passive"))
      (node (ref "U17") (pin "23") (pinfunction "PA0-WKUP(PA0)_23") (pintype "bidirectional"))
    )
    (net (code "121") (name "uSlave_RX") (class "Default")
      (node (ref "R59") (pin "1") (pinfunction "1_1") (pintype "passive"))
      (node (ref "U17") (pin "48") (pinfunction "PB11_48") (pintype "bidirectional"))
    )
    (net (code "122") (name "uSlave_RX_2") (class "Default")
      (node (ref "R59") (pin "2") (pinfunction "2_2") (pintype "passive"))
    )
    (net (code "123") (name "uSlave_TX") (class "Default")
      (node (ref "R57") (pin "1") (pinfunction "1_1") (pintype "passive"))
      (node (ref "U17") (pin "47") (pinfunction "PB10_47") (pintype "bidirectional"))
    )
    (net (code "124") (name "uSlave_TX_2") (class "Default")
      (node (ref "R57") (pin "2") (pinfunction "2_2") (pintype "passive"))
    )
    (net (code "125") (name "uUART2_RX") (class "Default")
      (node (ref "R65") (pin "1") (pinfunction "1_1") (pintype "passive"))
      (node (ref "U17") (pin "26") (pinfunction "PA3_26") (pintype "bidirectional"))
    )
    (net (code "126") (name "uUART2_RX_2") (class "Default")
      (node (ref "R160") (pin "1") (pinfunction "1_1") (pintype "passive"))
      (node (ref "R163") (pin "1") (pinfunction "1_1") (pintype "passive"))
      (node (ref "R65") (pin "2") (pinfunction "2_2") (pintype "passive"))
    )
    (net (code "127") (name "uUART2_TX") (class "Default")
      (node (ref "R60") (pin "1") (pinfunction "1_1") (pintype "passive"))
      (node (ref "U17") (pin "25") (pinfunction "PA2_25") (pintype "bidirectional"))
    )
    (net (code "128") (name "uUART2_TX_2") (class "Default")
      (node (ref "R162") (pin "1") (pinfunction "1_1") (pintype "passive"))
      (node (ref "R164") (pin "1") (pinfunction "1_1") (pintype "passive"))
      (node (ref "R60") (pin "2") (pinfunction "2_2") (pintype "passive"))
    )
    (net (code "129") (name "uWiFi_RX_2") (class "Default")
      (node (ref "R163") (pin "2") (pinfunction "2_2") (pintype "passive"))
    )
    (net (code "130") (name "uWiFi_TX_2") (class "Default")
      (node (ref "R164") (pin "2") (pinfunction "2_2") (pintype "passive"))
    )
    (net (code "131") (name "u_BAT_CUT_N") (class "Default")
      (node (ref "R148") (pin "1") (pinfunction "1_1") (pintype "passive"))
      (node (ref "U17") (pin "5") (pinfunction "PE6_5") (pintype "bidirectional"))
    )
    (net (code "132") (name "u_BAT_CUT_N_2") (class "Default")
      (node (ref "R148") (pin "2") (pinfunction "2_2") (pintype "passive"))
    )
    (net (code "133") (name "u_BAT_CUT_P") (class "Default")
      (node (ref "R147") (pin "1") (pinfunction "1_1") (pintype "passive"))
      (node (ref "U17") (pin "4") (pinfunction "PE5_4") (pintype "bidirectional"))
    )
    (net (code "134") (name "u_BAT_CUT_P_2") (class "Default")
      (node (ref "R147") (pin "2") (pinfunction "2_2") (pintype "passive"))
    )
    (net (code "135") (name "u_Do1") (class "Default")
      (node (ref "R72") (pin "1") (pinfunction "1_1") (pintype "passive"))
      (node (ref "U17") (pin "98") (pinfunction "PE1_98") (pintype "bidirectional"))
    )
    (net (code "136") (name "u_Do1_2") (class "Default")
      (node (ref "R72") (pin "2") (pinfunction "2_2") (pintype "passive"))
    )
    (net (code "137") (name "u_Do2") (class "Default")
      (node (ref "R95") (pin "1") (pinfunction "1_1") (pintype "passive"))
      (node (ref "U17") (pin "96") (pinfunction "PB9_96") (pintype "bidirectional"))
    )
    (net (code "138") (name "u_Do2_2") (class "Default")
      (node (ref "R95") (pin "2") (pinfunction "2_2") (pintype "passive"))
    )
    (net (code "139") (name "u_Relay1") (class "Default")
      (node (ref "R19") (pin "1") (pinfunction "1_1") (pintype "passive"))
      (node (ref "U17") (pin "95") (pinfunction "PB8_95") (pintype "bidirectional"))
    )
    (net (code "140") (name "u_Relay1_2") (class "Default")
      (node (ref "R19") (pin "2") (pinfunction "2_2") (pintype "passive"))
    )
    (net (code "141") (name "u_Relay2") (class "Default")
      (node (ref "R20") (pin "1") (pinfunction "1_1") (pintype "passive"))
      (node (ref "U17") (pin "91") (pinfunction "PB5_91") (pintype "bidirectional"))
    )
    (net (code "142") (name "u_Relay2_2") (class "Default")
      (node (ref "R20") (pin "2") (pinfunction "2_2") (pintype "passive"))
    )
    (net (code "143") (name "u_Relay3") (class "Default")
      (node (ref "R21") (pin "1") (pinfunction "1_1") (pintype "passive"))
      (node (ref "U17") (pin "90") (pinfunction "PB4(NJTRST)_90") (pintype "bidirectional"))
    )
    (net (code "144") (name "u_Relay3_2") (class "Default")
      (node (ref "R21") (pin "2") (pinfunction "2_2") (pintype "passive"))
    )
    (net (code "145") (name "u_Relay4") (class "Default")
      (node (ref "R22") (pin "1") (pinfunction "1_1") (pintype "passive"))
      (node (ref "U17") (pin "89") (pinfunction "PB3(JTDO/TRACESWO)_89") (pintype "bidirectional"))
    )
    (net (code "146") (name "u_Relay4_2") (class "Default")
      (node (ref "R22") (pin "2") (pinfunction "2_2") (pintype "passive"))
    )
    (net (code "147") (name "u_Relay5") (class "Default")
      (node (ref "R41") (pin "1") (pinfunction "1_1") (pintype "passive"))
      (node (ref "U17") (pin "88") (pinfunction "PD7_88") (pintype "bidirectional"))
    )
    (net (code "148") (name "u_Relay5_2") (class "Default")
      (node (ref "R41") (pin "2") (pinfunction "2_2") (pintype "passive"))
    )
    (net (code "149") (name "u_RelayGEN") (class "Default")
      (node (ref "R153") (pin "1") (pinfunction "1_1") (pintype "passive"))
      (node (ref "U17") (pin "61") (pinfunction "PD14_61") (pintype "bidirectional"))
    )
    (net (code "150") (name "u_RelayGEN_2") (class "Default")
      (node (ref "R153") (pin "2") (pinfunction "2_2") (pintype "passive"))
    )
    (net (code "151") (name "u_RelayGRID_N") (class "Default")
      (node (ref "R155") (pin "1") (pinfunction "1_1") (pintype "passive"))
      (node (ref "U17") (pin "59") (pinfunction "PD12_59") (pintype "bidirectional"))
    )
    (net (code "152") (name "u_RelayGRID_N_2") (class "Default")
      (node (ref "R155") (pin "2") (pinfunction "2_2") (pintype "passive"))
    )
    (net (code "153") (name "u_RelayGRID_P") (class "Default")
      (node (ref "R154") (pin "1") (pinfunction "1_1") (pintype "passive"))
      (node (ref "U17") (pin "60") (pinfunction "PD13_60") (pintype "bidirectional"))
    )
    (net (code "154") (name "u_RelayGRID_P_2") (class "Default")
      (node (ref "R154") (pin "2") (pinfunction "2_2") (pintype "passive"))
    )
    (net (code "155") (name "u_RelayGenHeat") (class "Default")
      (node (ref "R157") (pin "1") (pinfunction "1_1") (pintype "passive"))
      (node (ref "U17") (pin "7") (pinfunction "PC13_7") (pintype "bidirectional"))
    )
    (net (code "156") (name "u_RelayGenHeat_2") (class "Default")
      (node (ref "R157") (pin "2") (pinfunction "2_2") (pintype "passive"))
    )
    (net (code "157") (name "u_RelayLOAD") (class "Default")
      (node (ref "R156") (pin "1") (pinfunction "1_1") (pintype "passive"))
      (node (ref "U17") (pin "58") (pinfunction "PD11_58") (pintype "bidirectional"))
    )
    (net (code "158") (name "u_RelayLOAD_2") (class "Default")
      (node (ref "R156") (pin "2") (pinfunction "2_2") (pintype "passive"))
    )
    (net (code "159") (name "u_ds18b20") (class "Default")
      (node (ref "R146") (pin "1") (pinfunction "1_1") (pintype "passive"))
      (node (ref "U17") (pin "29") (pinfunction "PA4_29") (pintype "bidirectional"))
      (node (ref "ds18b20") (pin "2") (pinfunction "2_2") (pintype "passive"))
    )
    (net (code "160") (name "unconnected-(J4-Pad12)") (class "Default")
      (node (ref "J4") (pin "12") (pinfunction "12_12") (pintype "passive"))
    )
    (net (code "161") (name "unconnected-(U17A-PA8-Pad67)") (class "Default")
      (node (ref "U17") (pin "67") (pinfunction "PA8_67") (pintype "bidirectional"))
    )
    (net (code "162") (name "unconnected-(U17A-PB12-Pad51)") (class "Default")
      (node (ref "U17") (pin "51") (pinfunction "PB12_51") (pintype "bidirectional"))
    )
    (net (code "163") (name "unconnected-(U17A-PB13-Pad52)") (class "Default")
      (node (ref "U17") (pin "52") (pinfunction "PB13_52") (pintype "bidirectional"))
    )
    (net (code "164") (name "unconnected-(U17A-PB14-Pad53)") (class "Default")
      (node (ref "U17") (pin "53") (pinfunction "PB14_53") (pintype "bidirectional"))
    )
    (net (code "165") (name "unconnected-(U17A-PB15-Pad54)") (class "Default")
      (node (ref "U17") (pin "54") (pinfunction "PB15_54") (pintype "bidirectional"))
    )
    (net (code "166") (name "unconnected-(U17A-PC14-OSC32_IN(PC14)-Pad8)") (class "Default")
      (node (ref "U17") (pin "8") (pinfunction "PC14-OSC32_IN(PC14)_8") (pintype "bidirectional"))
    )
    (net (code "167") (name "unconnected-(U17A-PC15-OSC32_OUT(PC15)-Pad9)") (class "Default")
      (node (ref "U17") (pin "9") (pinfunction "PC15-OSC32_OUT(PC15)_9") (pintype "bidirectional"))
    )
    (net (code "168") (name "unconnected-(U17A-PD0-Pad81)") (class "Default")
      (node (ref "U17") (pin "81") (pinfunction "PD0_81") (pintype "bidirectional"))
    )
    (net (code "169") (name "unconnected-(U17A-PD6-Pad87)") (class "Default")
      (node (ref "U17") (pin "87") (pinfunction "PD6_87") (pintype "bidirectional"))
    )
    (net (code "170") (name "unconnected-(U17A-PD8-Pad55)") (class "Default")
      (node (ref "U17") (pin "55") (pinfunction "PD8_55") (pintype "bidirectional"))
    )
    (net (code "171") (name "unconnected-(U17A-PD9-Pad56)") (class "Default")
      (node (ref "U17") (pin "56") (pinfunction "PD9_56") (pintype "bidirectional"))
    )
    (net (code "172") (name "unconnected-(U17A-PE2-Pad1)") (class "Default")
      (node (ref "U17") (pin "1") (pinfunction "PE2_1") (pintype "bidirectional"))
    )
    (net (code "173") (name "unconnected-(U17A-PE3-Pad2)") (class "Default")
      (node (ref "U17") (pin "2") (pinfunction "PE3_2") (pintype "bidirectional"))
    )
    (net (code "174") (name "unconnected-(U17A-PE4-Pad3)") (class "Default")
      (node (ref "U17") (pin "3") (pinfunction "PE4_3") (pintype "bidirectional"))
    )
    (net (code "175") (name "unconnected-(U17A-PE11-Pad42)") (class "Default")
      (node (ref "U17") (pin "42") (pinfunction "PE11_42") (pintype "bidirectional"))
    )
    (net (code "176") (name "unconnected-(U17A-PE14-Pad45)") (class "Default")
      (node (ref "U17") (pin "45") (pinfunction "PE14_45") (pintype "bidirectional"))
    )
  )
)
